# DBG.net
KiCad netlist of a schematic drawn in Altium Designer
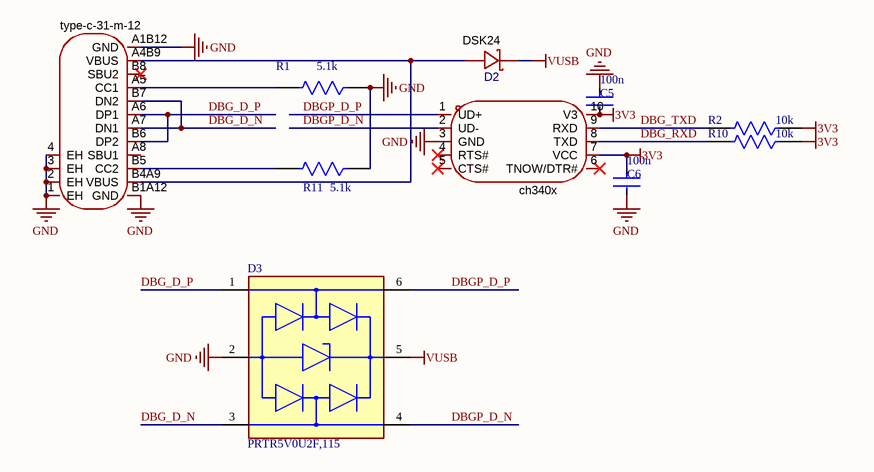
[diagram p0: DBG.SchDoc]

(export (version "E")
  (design (tool "Eeschema 10.0.6"))
  (components
    (comp (ref "C5")
      (value "100n")
      (footprint "CAP_0402")
      (description "C307331")
      (fields (field (name "TOLERANCE") "10%"))
      (libsource (lib "LEAKCAM") (part "CMP-03422-001116-1"))
    )
    (comp (ref "C6")
      (value "100n")
      (footprint "CAP_0402")
      (description "C307331")
      (fields (field (name "TOLERANCE") "10%"))
      (libsource (lib "LEAKCAM") (part "CMP-03422-001116-1"))
    )
    (comp (ref "D2")
      (value "DSK24")
      (footprint "DSK24")
      (description "C22466352")
      (fields (field (name "MANUFACTURER") "MDD(辰达半导体)"))
      (libsource (lib "LEAKCAM") (part "dsk24_c64890"))
    )
    (comp (ref "D3")
      (value "PRTR5V0U2F,115")
      (footprint "FP-SOT886-MFG")
      (description "C478118")
      (fields
        (field (name "OCTOPART") "https://octopart.com/prtr5v0u2f%2C115-nexperia-78741690")
        (field (name "MANUFACTURER") "Nexperia")
      )
      (libsource (lib "LEAKCAM") (part "CMP-14436-000003-1"))
    )
    (comp (ref "R1")
      (value "5.1k")
      (footprint "RES_0402")
      (description "C25905")
      (fields (field (name "TOLERANCE") "1%"))
      (libsource (lib "LEAKCAM") (part "CMP-03412-016018-1"))
    )
    (comp (ref "R2")
      (value "10k")
      (footprint "RES_0402")
      (description "C25744")
      (fields (field (name "TOLERANCE") "1%"))
      (libsource (lib "LEAKCAM") (part "CMP-03412-016018-1"))
    )
    (comp (ref "R10")
      (value "10k")
      (footprint "RES_0402")
      (description "C25744")
      (fields (field (name "TOLERANCE") "1%"))
      (libsource (lib "LEAKCAM") (part "CMP-03412-016018-1"))
    )
    (comp (ref "R11")
      (value "5.1k")
      (footprint "RES_0402")
      (description "C25905")
      (fields (field (name "TOLERANCE") "1%"))
      (libsource (lib "LEAKCAM") (part "CMP-03412-016018-1"))
    )
    (comp (ref "U2")
      (value "ch340x")
      (footprint "ch340x")
      (description "C3035748")
      (fields (field (name "MANUFACTURER") "WCH(南京沁恒)") (field (name "MANUFACTURER PART") "CH340X"))
      (libsource (lib "LEAKCAM") (part "ch340x"))
    )
    (comp (ref "USBC2")
      (value "type-c-31-m-12")
      (footprint "TYPE-C-31-M-12")
      (description "C165948")
      (fields (field (name "MANUFACTURER") "韩国韩荣") (field (name "MANUFACTURERPART") "TYPE-C-31-M-12"))
      (libsource (lib "LEAKCAM") (part "type-c-31-m-12"))
    )
  )
  (nets
    (net (code "1") (name "/DBGP_D_N") (class "Default")
      (node (ref "D3") (pin "4") (pinfunction "I/O2_4") (pintype "passive"))
      (node (ref "U2") (pin "2") (pinfunction "UD-_2") (pintype "passive"))
    )
    (net (code "2") (name "/DBGP_D_P") (class "Default")
      (node (ref "D3") (pin "6") (pinfunction "I/O1_6") (pintype "passive"))
      (node (ref "U2") (pin "1") (pinfunction "UD+_1") (pintype "passive"))
    )
    (net (code "3") (name "/DBG_D_N") (class "Default")
      (node (ref "D3") (pin "3") (pinfunction "I/O2_3") (pintype "passive"))
      (node (ref "USBC2") (pin "A7") (pinfunction "DN1_A7") (pintype "passive"))
      (node (ref "USBC2") (pin "B7") (pinfunction "DN2_B7") (pintype "passive"))
    )
    (net (code "4") (name "/DBG_D_P") (class "Default")
      (node (ref "D3") (pin "1") (pinfunction "I/O1_1") (pintype "passive"))
      (node (ref "USBC2") (pin "A6") (pinfunction "DP1_A6") (pintype "passive"))
      (node (ref "USBC2") (pin "B6") (pinfunction "DP2_B6") (pintype "passive"))
    )
    (net (code "5") (name "/DBG_RXD") (class "Default")
      (node (ref "R10") (pin "2") (pinfunction "2_2") (pintype "passive"))
      (node (ref "U2") (pin "8") (pinfunction "TXD_8") (pintype "passive"))
    )
    (net (code "6") (name "/DBG_TXD") (class "Default")
      (node (ref "R2") (pin "2") (pinfunction "2_2") (pintype "passive"))
      (node (ref "U2") (pin "9") (pinfunction "RXD_9") (pintype "passive"))
    )
    (net (code "7") (name "3V3") (class "Default")
      (node (ref "C5") (pin "2") (pinfunction "2_2") (pintype "passive"))
      (node (ref "C6") (pin "1") (pinfunction "1_1") (pintype "passive"))
      (node (ref "R10") (pin "1") (pinfunction "1_1") (pintype "passive"))
      (node (ref "R2") (pin "1") (pinfunction "1_1") (pintype "passive"))
      (node (ref "U2") (pin "10") (pinfunction "V3_10") (pintype "passive"))
      (node (ref "U2") (pin "7") (pinfunction "VCC_7") (pintype "passive"))
    )
    (net (code "8") (name "GND") (class "Default")
      (node (ref "C5") (pin "1") (pinfunction "1_1") (pintype "passive"))
      (node (ref "C6") (pin "2") (pinfunction "2_2") (pintype "passive"))
      (node (ref "D3") (pin "2") (pinfunction "GND_2") (pintype "power_in"))
      (node (ref "R1") (pin "1") (pinfunction "1_1") (pintype "passive"))
      (node (ref "R11") (pin "1") (pinfunction "1_1") (pintype "passive"))
      (node (ref "U2") (pin "3") (pinfunction "GND_3") (pintype "passive"))
      (node (ref "USBC2") (pin "1") (pinfunction "EH_1") (pintype "passive"))
      (node (ref "USBC2") (pin "2") (pinfunction "EH_2") (pintype "passive"))
      (node (ref "USBC2") (pin "3") (pinfunction "EH_3") (pintype "passive"))
      (node (ref "USBC2") (pin "4") (pinfunction "EH_4") (pintype "passive"))
      (node (ref "USBC2") (pin "A1B12") (pinfunction "GND_A1B12") (pintype "passive"))
      (node (ref "USBC2") (pin "B1A12") (pinfunction "GND_B1A12") (pintype "passive"))
    )
    (net (code "9") (name "Net-(D2-A)") (class "Default")
      (node (ref "D2") (pin "2") (pinfunction "A_2") (pintype "passive"))
      (node (ref "USBC2") (pin "A4B9") (pinfunction "VBUS_A4B9") (pintype "passive"))
      (node (ref "USBC2") (pin "B4A9") (pinfunction "VBUS_B4A9") (pintype "passive"))
    )
    (net (code "10") (name "Net-(USBC2-CC1)") (class "Default")
      (node (ref "R1") (pin "2") (pinfunction "2_2") (pintype "passive"))
      (node (ref "USBC2") (pin "A5") (pinfunction "CC1_A5") (pintype "passive"))
    )
    (net (code "11") (name "Net-(USBC2-CC2)") (class "Default")
      (node (ref "R11") (pin "2") (pinfunction "2_2") (pintype "passive"))
      (node (ref "USBC2") (pin "B5") (pinfunction "CC2_B5") (pintype "passive"))
    )
    (net (code "12") (name "VUSB") (class "Default")
      (node (ref "D2") (pin "1") (pinfunction "K_1") (pintype "passive"))
      (node (ref "D3") (pin "5") (pinfunction "VCC_5") (pintype "power_in"))
    )
    (net (code "13") (name "unconnected-(U2-CTS#-Pad5)") (class "Default")
      (node (ref "U2") (pin "5") (pinfunction "CTS#_5") (pintype "passive+no_connect"))
    )
    (net (code "14") (name "unconnected-(U2-RTS#-Pad4)") (class "Default")
      (node (ref "U2") (pin "4") (pinfunction "RTS#_4") (pintype "passive+no_connect"))
    )
    (net (code "15") (name "unconnected-(U2-TNOW{slash}DTR#-Pad6)") (class "Default")
      (node (ref "U2") (pin "6") (pinfunction "TNOW/DTR#_6") (pintype "passive+no_connect"))
    )
    (net (code "16") (name "unconnected-(USBC2-SBU1-PadA8)") (class "Default")
      (node (ref "USBC2") (pin "A8") (pinfunction "SBU1_A8") (pintype "passive"))
    )
    (net (code "17") (name "unconnected-(USBC2-SBU2-PadB8)") (class "Default")
      (node (ref "USBC2") (pin "B8") (pinfunction "SBU2_B8") (pintype "passive+no_connect"))
    )
  )
)
